# encore_Control_Board.net
KiCad netlist of a schematic drawn in EAGLE
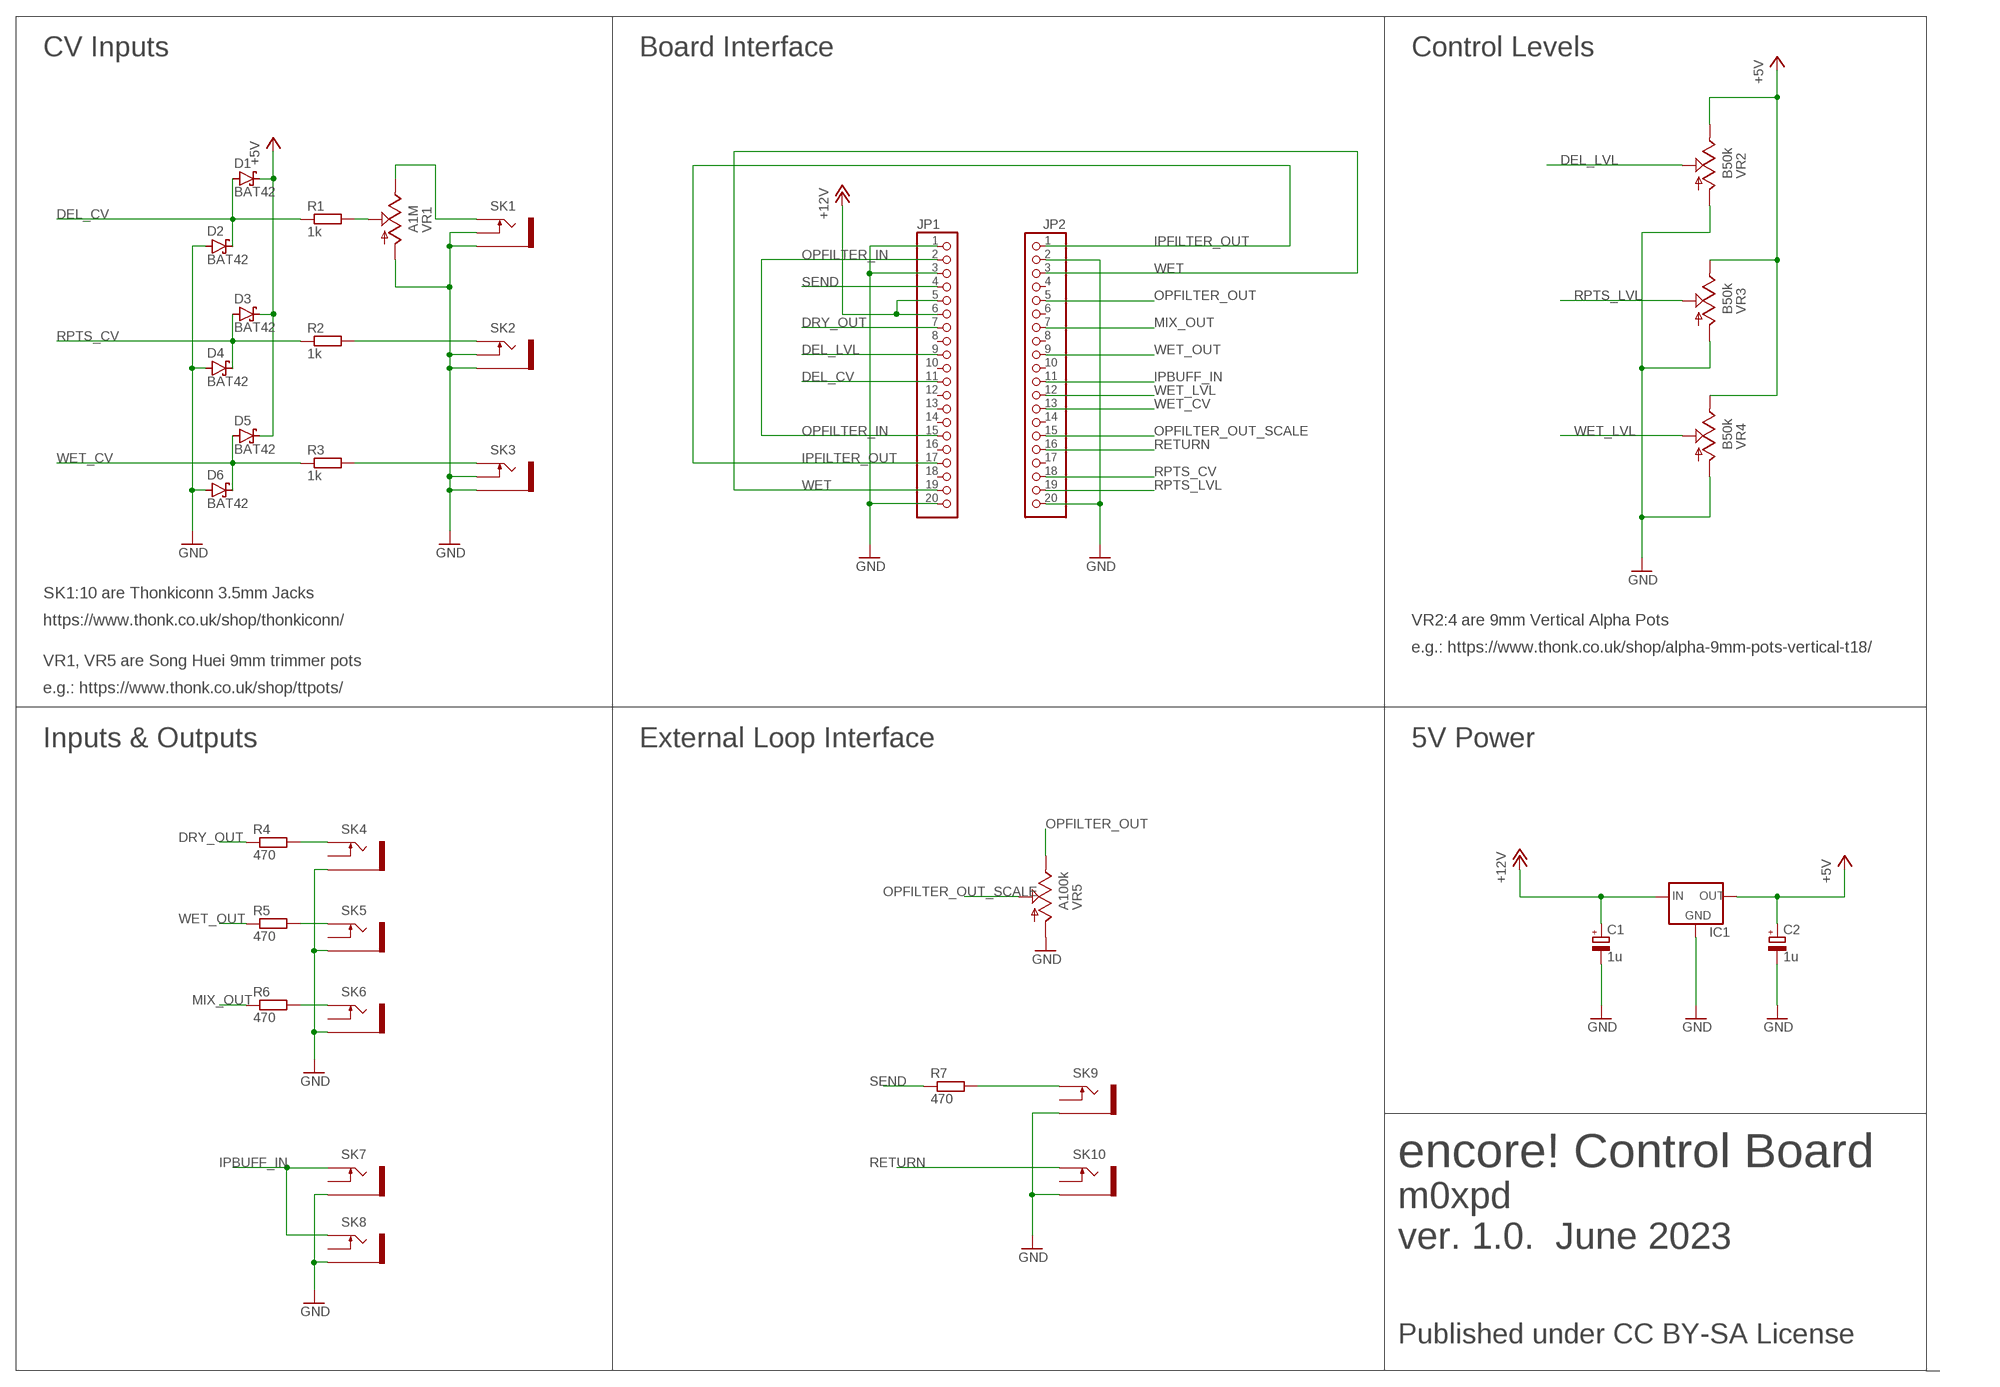
[diagram p0: schematic, sheet 1]

(export (version "E")
  (design (tool "Eeschema 10.0.6"))
  (components
    (comp (ref "C1")
      (value "1u")
      (footprint "eagle-import:E2,5-5")
      (libsource (lib "eagle-import") (part "CPOL-EUE2.5-5"))
    )
    (comp (ref "C2")
      (value "1u")
      (footprint "eagle-import:E2,5-5")
      (libsource (lib "eagle-import") (part "CPOL-EUE2.5-5"))
    )
    (comp (ref "D1")
      (value "BAT42")
      (footprint "eagle-import:DO35-10")
      (libsource (lib "eagle-import") (part "BAT42"))
    )
    (comp (ref "D2")
      (value "BAT42")
      (footprint "eagle-import:DO35-10")
      (libsource (lib "eagle-import") (part "BAT42"))
    )
    (comp (ref "D3")
      (value "BAT42")
      (footprint "eagle-import:DO35-10")
      (libsource (lib "eagle-import") (part "BAT42"))
    )
    (comp (ref "D4")
      (value "BAT42")
      (footprint "eagle-import:DO35-10")
      (libsource (lib "eagle-import") (part "BAT42"))
    )
    (comp (ref "D5")
      (value "BAT42")
      (footprint "eagle-import:DO35-10")
      (libsource (lib "eagle-import") (part "BAT42"))
    )
    (comp (ref "D6")
      (value "BAT42")
      (footprint "eagle-import:DO35-10")
      (libsource (lib "eagle-import") (part "BAT42"))
    )
    (comp (ref "IC1")
      (value "78LXX")
      (footprint "eagle-import:78LXX")
      (libsource (lib "eagle-import") (part "78LXX"))
    )
    (comp (ref "JP1")
      (value "PINHD-1X20")
      (footprint "eagle-import:1X20")
      (libsource (lib "eagle-import") (part "PINHD-1X20"))
    )
    (comp (ref "JP2")
      (value "PINHD-1X20")
      (footprint "eagle-import:1X20")
      (libsource (lib "eagle-import") (part "PINHD-1X20"))
    )
    (comp (ref "R1")
      (value "1k")
      (footprint "eagle-import:0204_7")
      (libsource (lib "eagle-import") (part "R-EU_0204/7"))
    )
    (comp (ref "R2")
      (value "1k")
      (footprint "eagle-import:0204_7")
      (libsource (lib "eagle-import") (part "R-EU_0204/7"))
    )
    (comp (ref "R3")
      (value "1k")
      (footprint "eagle-import:0204_7")
      (libsource (lib "eagle-import") (part "R-EU_0204/7"))
    )
    (comp (ref "R4")
      (value "470")
      (footprint "eagle-import:0204_7")
      (libsource (lib "eagle-import") (part "R-EU_0204/7"))
    )
    (comp (ref "R5")
      (value "470")
      (footprint "eagle-import:0204_7")
      (libsource (lib "eagle-import") (part "R-EU_0204/7"))
    )
    (comp (ref "R6")
      (value "470")
      (footprint "eagle-import:0204_7")
      (libsource (lib "eagle-import") (part "R-EU_0204/7"))
    )
    (comp (ref "R7")
      (value "470")
      (footprint "eagle-import:0204_7")
      (libsource (lib "eagle-import") (part "R-EU_0204/7"))
    )
    (comp (ref "SK1")
      (value "THONKICONN_JACK")
      (footprint "eagle-import:WQP-PJ301M-12_JACK")
      (libsource (lib "eagle-import") (part "THONKICONN_JACK"))
    )
    (comp (ref "SK2")
      (value "THONKICONN_JACK")
      (footprint "eagle-import:WQP-PJ301M-12_JACK")
      (libsource (lib "eagle-import") (part "THONKICONN_JACK"))
    )
    (comp (ref "SK3")
      (value "THONKICONN_JACK")
      (footprint "eagle-import:WQP-PJ301M-12_JACK")
      (libsource (lib "eagle-import") (part "THONKICONN_JACK"))
    )
    (comp (ref "SK4")
      (value "THONKICONN_JACK")
      (footprint "eagle-import:WQP-PJ301M-12_JACK")
      (libsource (lib "eagle-import") (part "THONKICONN_JACK"))
    )
    (comp (ref "SK5")
      (value "THONKICONN_JACK")
      (footprint "eagle-import:WQP-PJ301M-12_JACK")
      (libsource (lib "eagle-import") (part "THONKICONN_JACK"))
    )
    (comp (ref "SK6")
      (value "THONKICONN_JACK")
      (footprint "eagle-import:WQP-PJ301M-12_JACK")
      (libsource (lib "eagle-import") (part "THONKICONN_JACK"))
    )
    (comp (ref "SK7")
      (value "THONKICONN_JACK")
      (footprint "eagle-import:WQP-PJ301M-12_JACK")
      (libsource (lib "eagle-import") (part "THONKICONN_JACK"))
    )
    (comp (ref "SK8")
      (value "THONKICONN_JACK")
      (footprint "eagle-import:WQP-PJ301M-12_JACK")
      (libsource (lib "eagle-import") (part "THONKICONN_JACK"))
    )
    (comp (ref "SK9")
      (value "THONKICONN_JACK")
      (footprint "eagle-import:WQP-PJ301M-12_JACK")
      (libsource (lib "eagle-import") (part "THONKICONN_JACK"))
    )
    (comp (ref "SK10")
      (value "THONKICONN_JACK")
      (footprint "eagle-import:WQP-PJ301M-12_JACK")
      (libsource (lib "eagle-import") (part "THONKICONN_JACK"))
    )
    (comp (ref "VR1")
      (value "A1M")
      (footprint "eagle-import:9MM_SNAP-IN_POT")
      (libsource (lib "eagle-import") (part "9MM_SNAP-IN_POT_"))
    )
    (comp (ref "VR2")
      (value "B50k")
      (footprint "eagle-import:9MM_SNAP-IN_POT")
      (libsource (lib "eagle-import") (part "9MM_SNAP-IN_POT_"))
    )
    (comp (ref "VR3")
      (value "B50k")
      (footprint "eagle-import:9MM_SNAP-IN_POT")
      (libsource (lib "eagle-import") (part "9MM_SNAP-IN_POT_"))
    )
    (comp (ref "VR4")
      (value "B50k")
      (footprint "eagle-import:9MM_SNAP-IN_POT")
      (libsource (lib "eagle-import") (part "9MM_SNAP-IN_POT_"))
    )
    (comp (ref "VR5")
      (value "A100k")
      (footprint "eagle-import:9MM_SNAP-IN_POT")
      (libsource (lib "eagle-import") (part "9MM_SNAP-IN_POT_"))
    )
  )
  (nets
    (net (code "1") (name "+5V") (class "Default")
      (node (ref "C2") (pin "+") (pinfunction "+_+") (pintype "passive"))
      (node (ref "D1") (pin "C") (pinfunction "C_C") (pintype "passive"))
      (node (ref "D3") (pin "C") (pinfunction "C_C") (pintype "passive"))
      (node (ref "D5") (pin "C") (pinfunction "C_C") (pintype "passive"))
      (node (ref "IC1") (pin "OUT") (pinfunction "OUT_OUT") (pintype "passive"))
      (node (ref "VR2") (pin "3") (pinfunction "E_3") (pintype "passive"))
      (node (ref "VR3") (pin "3") (pinfunction "E_3") (pintype "passive"))
      (node (ref "VR4") (pin "3") (pinfunction "E_3") (pintype "passive"))
    )
    (net (code "2") (name "+12V") (class "Default")
      (node (ref "C1") (pin "+") (pinfunction "+_+") (pintype "passive"))
      (node (ref "IC1") (pin "IN") (pinfunction "IN_IN") (pintype "input"))
      (node (ref "JP1") (pin "5") (pinfunction "5_5") (pintype "passive"))
      (node (ref "JP1") (pin "6") (pinfunction "6_6") (pintype "passive"))
    )
    (net (code "3") (name "/DEL_CV") (class "Default")
      (node (ref "D1") (pin "A") (pinfunction "A_A") (pintype "passive"))
      (node (ref "D2") (pin "C") (pinfunction "C_C") (pintype "passive"))
      (node (ref "JP1") (pin "11") (pinfunction "11_11") (pintype "passive"))
      (node (ref "R1") (pin "1") (pinfunction "1_1") (pintype "passive"))
    )
    (net (code "4") (name "/DEL_LVL") (class "Default")
      (node (ref "JP1") (pin "9") (pinfunction "9_9") (pintype "passive"))
      (node (ref "VR2") (pin "2") (pinfunction "S_2") (pintype "passive"))
    )
    (net (code "5") (name "/DRY_OUT") (class "Default")
      (node (ref "JP1") (pin "7") (pinfunction "7_7") (pintype "passive"))
      (node (ref "R4") (pin "1") (pinfunction "1_1") (pintype "passive"))
    )
    (net (code "6") (name "/IPBUFF_IN") (class "Default")
      (node (ref "JP2") (pin "11") (pinfunction "11_11") (pintype "passive"))
      (node (ref "SK7") (pin "P$1_TIP") (pinfunction "TIP_P$1_TIP") (pintype "passive"))
      (node (ref "SK8") (pin "P$1_TIP") (pinfunction "TIP_P$1_TIP") (pintype "passive"))
    )
    (net (code "7") (name "/IPFILTER_OUT") (class "Default")
      (node (ref "JP1") (pin "17") (pinfunction "17_17") (pintype "passive"))
      (node (ref "JP2") (pin "1") (pinfunction "1_1") (pintype "passive"))
    )
    (net (code "8") (name "/MIX_OUT") (class "Default")
      (node (ref "JP2") (pin "7") (pinfunction "7_7") (pintype "passive"))
      (node (ref "R6") (pin "1") (pinfunction "1_1") (pintype "passive"))
    )
    (net (code "9") (name "/OPFILTER_IN") (class "Default")
      (node (ref "JP1") (pin "15") (pinfunction "15_15") (pintype "passive"))
      (node (ref "JP1") (pin "2") (pinfunction "2_2") (pintype "passive"))
    )
    (net (code "10") (name "/OPFILTER_OUT") (class "Default")
      (node (ref "JP2") (pin "5") (pinfunction "5_5") (pintype "passive"))
      (node (ref "VR5") (pin "3") (pinfunction "E_3") (pintype "passive"))
    )
    (net (code "11") (name "/OPFILTER_OUT_SCALE") (class "Default")
      (node (ref "JP2") (pin "15") (pinfunction "15_15") (pintype "passive"))
      (node (ref "VR5") (pin "2") (pinfunction "S_2") (pintype "passive"))
    )
    (net (code "12") (name "/RETURN") (class "Default")
      (node (ref "JP2") (pin "16") (pinfunction "16_16") (pintype "passive"))
      (node (ref "SK10") (pin "P$1_TIP") (pinfunction "TIP_P$1_TIP") (pintype "passive"))
    )
    (net (code "13") (name "/RPTS_CV") (class "Default")
      (node (ref "D3") (pin "A") (pinfunction "A_A") (pintype "passive"))
      (node (ref "D4") (pin "C") (pinfunction "C_C") (pintype "passive"))
      (node (ref "JP2") (pin "18") (pinfunction "18_18") (pintype "passive"))
      (node (ref "R2") (pin "1") (pinfunction "1_1") (pintype "passive"))
    )
    (net (code "14") (name "/RPTS_LVL") (class "Default")
      (node (ref "JP2") (pin "19") (pinfunction "19_19") (pintype "passive"))
      (node (ref "VR3") (pin "2") (pinfunction "S_2") (pintype "passive"))
    )
    (net (code "15") (name "/SEND") (class "Default")
      (node (ref "JP1") (pin "4") (pinfunction "4_4") (pintype "passive"))
      (node (ref "R7") (pin "1") (pinfunction "1_1") (pintype "passive"))
    )
    (net (code "16") (name "/WET") (class "Default")
      (node (ref "JP1") (pin "19") (pinfunction "19_19") (pintype "passive"))
      (node (ref "JP2") (pin "3") (pinfunction "3_3") (pintype "passive"))
    )
    (net (code "17") (name "/WET_CV") (class "Default")
      (node (ref "D5") (pin "A") (pinfunction "A_A") (pintype "passive"))
      (node (ref "D6") (pin "C") (pinfunction "C_C") (pintype "passive"))
      (node (ref "JP2") (pin "13") (pinfunction "13_13") (pintype "passive"))
      (node (ref "R3") (pin "1") (pinfunction "1_1") (pintype "passive"))
    )
    (net (code "18") (name "/WET_LVL") (class "Default")
      (node (ref "JP2") (pin "12") (pinfunction "12_12") (pintype "passive"))
      (node (ref "VR4") (pin "2") (pinfunction "S_2") (pintype "passive"))
    )
    (net (code "19") (name "/WET_OUT") (class "Default")
      (node (ref "JP2") (pin "9") (pinfunction "9_9") (pintype "passive"))
      (node (ref "R5") (pin "1") (pinfunction "1_1") (pintype "passive"))
    )
    (net (code "20") (name "GND") (class "Default")
      (node (ref "C1") (pin "-") (pinfunction "-_-") (pintype "passive"))
      (node (ref "C2") (pin "-") (pinfunction "-_-") (pintype "passive"))
      (node (ref "D2") (pin "A") (pinfunction "A_A") (pintype "passive"))
      (node (ref "D4") (pin "A") (pinfunction "A_A") (pintype "passive"))
      (node (ref "D6") (pin "A") (pinfunction "A_A") (pintype "passive"))
      (node (ref "IC1") (pin "GND") (pinfunction "GND_GND") (pintype "input"))
      (node (ref "JP1") (pin "1") (pinfunction "1_1") (pintype "passive"))
      (node (ref "JP1") (pin "20") (pinfunction "20_20") (pintype "passive"))
      (node (ref "JP1") (pin "3") (pinfunction "3_3") (pintype "passive"))
      (node (ref "JP2") (pin "2") (pinfunction "2_2") (pintype "passive"))
      (node (ref "JP2") (pin "20") (pinfunction "20_20") (pintype "passive"))
      (node (ref "SK1") (pin "P$2_SWITCH") (pinfunction "SWITCH_P$2_SWITCH") (pintype "passive"))
      (node (ref "SK1") (pin "P$3_SLEEVE") (pinfunction "SLEEVE_P$3_SLEEVE") (pintype "passive"))
      (node (ref "SK10") (pin "P$3_SLEEVE") (pinfunction "SLEEVE_P$3_SLEEVE") (pintype "passive"))
      (node (ref "SK2") (pin "P$2_SWITCH") (pinfunction "SWITCH_P$2_SWITCH") (pintype "passive"))
      (node (ref "SK2") (pin "P$3_SLEEVE") (pinfunction "SLEEVE_P$3_SLEEVE") (pintype "passive"))
      (node (ref "SK3") (pin "P$2_SWITCH") (pinfunction "SWITCH_P$2_SWITCH") (pintype "passive"))
      (node (ref "SK3") (pin "P$3_SLEEVE") (pinfunction "SLEEVE_P$3_SLEEVE") (pintype "passive"))
      (node (ref "SK4") (pin "P$3_SLEEVE") (pinfunction "SLEEVE_P$3_SLEEVE") (pintype "passive"))
      (node (ref "SK5") (pin "P$3_SLEEVE") (pinfunction "SLEEVE_P$3_SLEEVE") (pintype "passive"))
      (node (ref "SK6") (pin "P$3_SLEEVE") (pinfunction "SLEEVE_P$3_SLEEVE") (pintype "passive"))
      (node (ref "SK7") (pin "P$3_SLEEVE") (pinfunction "SLEEVE_P$3_SLEEVE") (pintype "passive"))
      (node (ref "SK8") (pin "P$3_SLEEVE") (pinfunction "SLEEVE_P$3_SLEEVE") (pintype "passive"))
      (node (ref "SK9") (pin "P$3_SLEEVE") (pinfunction "SLEEVE_P$3_SLEEVE") (pintype "passive"))
      (node (ref "VR1") (pin "1") (pinfunction "A_1") (pintype "passive"))
      (node (ref "VR2") (pin "1") (pinfunction "A_1") (pintype "passive"))
      (node (ref "VR3") (pin "1") (pinfunction "A_1") (pintype "passive"))
      (node (ref "VR4") (pin "1") (pinfunction "A_1") (pintype "passive"))
      (node (ref "VR5") (pin "1") (pinfunction "A_1") (pintype "passive"))
    )
    (net (code "21") (name "Net-(SK1-TIP)") (class "Default")
      (node (ref "SK1") (pin "P$1_TIP") (pinfunction "TIP_P$1_TIP") (pintype "passive"))
      (node (ref "VR1") (pin "3") (pinfunction "E_3") (pintype "passive"))
    )
    (net (code "22") (name "Net-(SK2-TIP)") (class "Default")
      (node (ref "R2") (pin "2") (pinfunction "2_2") (pintype "passive"))
      (node (ref "SK2") (pin "P$1_TIP") (pinfunction "TIP_P$1_TIP") (pintype "passive"))
    )
    (net (code "23") (name "Net-(SK3-TIP)") (class "Default")
      (node (ref "R3") (pin "2") (pinfunction "2_2") (pintype "passive"))
      (node (ref "SK3") (pin "P$1_TIP") (pinfunction "TIP_P$1_TIP") (pintype "passive"))
    )
    (net (code "24") (name "Net-(SK4-TIP)") (class "Default")
      (node (ref "R4") (pin "2") (pinfunction "2_2") (pintype "passive"))
      (node (ref "SK4") (pin "P$1_TIP") (pinfunction "TIP_P$1_TIP") (pintype "passive"))
    )
    (net (code "25") (name "Net-(SK5-TIP)") (class "Default")
      (node (ref "R5") (pin "2") (pinfunction "2_2") (pintype "passive"))
      (node (ref "SK5") (pin "P$1_TIP") (pinfunction "TIP_P$1_TIP") (pintype "passive"))
    )
    (net (code "26") (name "Net-(SK6-TIP)") (class "Default")
      (node (ref "R6") (pin "2") (pinfunction "2_2") (pintype "passive"))
      (node (ref "SK6") (pin "P$1_TIP") (pinfunction "TIP_P$1_TIP") (pintype "passive"))
    )
    (net (code "27") (name "Net-(SK9-TIP)") (class "Default")
      (node (ref "R7") (pin "2") (pinfunction "2_2") (pintype "passive"))
      (node (ref "SK9") (pin "P$1_TIP") (pinfunction "TIP_P$1_TIP") (pintype "passive"))
    )
    (net (code "28") (name "Net-(VR1-S)") (class "Default")
      (node (ref "R1") (pin "2") (pinfunction "2_2") (pintype "passive"))
      (node (ref "VR1") (pin "2") (pinfunction "S_2") (pintype "passive"))
    )
    (net (code "29") (name "unconnected-(JP1-Pad8)") (class "Default")
      (node (ref "JP1") (pin "8") (pinfunction "8_8") (pintype "passive"))
    )
    (net (code "30") (name "unconnected-(JP1-Pad10)") (class "Default")
      (node (ref "JP1") (pin "10") (pinfunction "10_10") (pintype "passive"))
    )
    (net (code "31") (name "unconnected-(JP1-Pad12)") (class "Default")
      (node (ref "JP1") (pin "12") (pinfunction "12_12") (pintype "passive"))
    )
    (net (code "32") (name "unconnected-(JP1-Pad13)") (class "Default")
      (node (ref "JP1") (pin "13") (pinfunction "13_13") (pintype "passive"))
    )
    (net (code "33") (name "unconnected-(JP1-Pad14)") (class "Default")
      (node (ref "JP1") (pin "14") (pinfunction "14_14") (pintype "passive"))
    )
    (net (code "34") (name "unconnected-(JP1-Pad16)") (class "Default")
      (node (ref "JP1") (pin "16") (pinfunction "16_16") (pintype "passive"))
    )
    (net (code "35") (name "unconnected-(JP1-Pad18)") (class "Default")
      (node (ref "JP1") (pin "18") (pinfunction "18_18") (pintype "passive"))
    )
    (net (code "36") (name "unconnected-(JP2-Pad4)") (class "Default")
      (node (ref "JP2") (pin "4") (pinfunction "4_4") (pintype "passive"))
    )
    (net (code "37") (name "unconnected-(JP2-Pad6)") (class "Default")
      (node (ref "JP2") (pin "6") (pinfunction "6_6") (pintype "passive"))
    )
    (net (code "38") (name "unconnected-(JP2-Pad8)") (class "Default")
      (node (ref "JP2") (pin "8") (pinfunction "8_8") (pintype "passive"))
    )
    (net (code "39") (name "unconnected-(JP2-Pad10)") (class "Default")
      (node (ref "JP2") (pin "10") (pinfunction "10_10") (pintype "passive"))
    )
    (net (code "40") (name "unconnected-(JP2-Pad14)") (class "Default")
      (node (ref "JP2") (pin "14") (pinfunction "14_14") (pintype "passive"))
    )
    (net (code "41") (name "unconnected-(JP2-Pad17)") (class "Default")
      (node (ref "JP2") (pin "17") (pinfunction "17_17") (pintype "passive"))
    )
    (net (code "42") (name "unconnected-(SK4-SWITCH-PadP$2_SWITCH)") (class "Default")
      (node (ref "SK4") (pin "P$2_SWITCH") (pinfunction "SWITCH_P$2_SWITCH") (pintype "passive"))
    )
    (net (code "43") (name "unconnected-(SK5-SWITCH-PadP$2_SWITCH)") (class "Default")
      (node (ref "SK5") (pin "P$2_SWITCH") (pinfunction "SWITCH_P$2_SWITCH") (pintype "passive"))
    )
    (net (code "44") (name "unconnected-(SK6-SWITCH-PadP$2_SWITCH)") (class "Default")
      (node (ref "SK6") (pin "P$2_SWITCH") (pinfunction "SWITCH_P$2_SWITCH") (pintype "passive"))
    )
    (net (code "45") (name "unconnected-(SK7-SWITCH-PadP$2_SWITCH)") (class "Default")
      (node (ref "SK7") (pin "P$2_SWITCH") (pinfunction "SWITCH_P$2_SWITCH") (pintype "passive"))
    )
    (net (code "46") (name "unconnected-(SK8-SWITCH-PadP$2_SWITCH)") (class "Default")
      (node (ref "SK8") (pin "P$2_SWITCH") (pinfunction "SWITCH_P$2_SWITCH") (pintype "passive"))
    )
    (net (code "47") (name "unconnected-(SK9-SWITCH-PadP$2_SWITCH)") (class "Default")
      (node (ref "SK9") (pin "P$2_SWITCH") (pinfunction "SWITCH_P$2_SWITCH") (pintype "passive"))
    )
    (net (code "48") (name "unconnected-(SK10-SWITCH-PadP$2_SWITCH)") (class "Default")
      (node (ref "SK10") (pin "P$2_SWITCH") (pinfunction "SWITCH_P$2_SWITCH") (pintype "passive"))
    )
  )
)
